# 4_-RF.net
KiCad netlist of a schematic drawn in Altium Designer
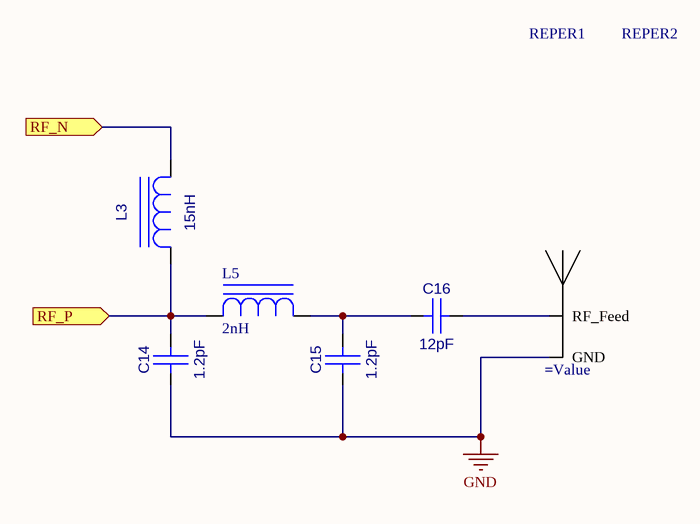
[diagram p0: [4]-RF.SchDoc]

(export (version "E")
  (design (tool "Eeschema 10.0.6"))
  (components
    (comp (ref "=Value")
      (value "ANTENNA_IFA_245_1MM")
      (footprint "IFA245_1mm")
      (description "Antenna 2.45GHz")
      (libsource (lib "fizik_lib") (part "ANTENNA_IFA_245_1MM"))
    )
    (comp (ref "C14")
      (value "1.2pF")
      (footprint "CC0603")
      (description "CC0603")
      (libsource (lib "gprs_modem_2") (part "CC0603"))
    )
    (comp (ref "C15")
      (value "1.2pF")
      (footprint "CC0603")
      (description "CC0603")
      (libsource (lib "gprs_modem_2") (part "CC0603"))
    )
    (comp (ref "C16")
      (value "12pF")
      (footprint "CC0603")
      (description "CC0603")
      (libsource (lib "gprs_modem_2") (part "CC0603"))
    )
    (comp (ref "L3")
      (value "15nH")
      (footprint "L0603")
      (description "L0603")
      (libsource (lib "fizik_lib") (part "L0603"))
    )
    (comp (ref "L5")
      (value "2nH")
      (footprint "L0402")
      (description "L0402")
      (libsource (lib "gprs_modem_2") (part "L0402"))
    )
    (comp (ref "REPER1")
      (value "REPER1.2")
      (footprint "REPER1.2")
      (libsource (lib "gprs_modem_2") (part "REPER1.2"))
    )
    (comp (ref "REPER2")
      (value "REPER1.2")
      (footprint "REPER1.2")
      (libsource (lib "gprs_modem_2") (part "REPER1.2"))
    )
  )
  (nets
    (net (code "1") (name "/RF_N") (class "Default")
      (node (ref "L3") (pin "2") (pinfunction "C_2") (pintype "passive"))
    )
    (net (code "2") (name "/RF_P") (class "Default")
      (node (ref "C14") (pin "2") (pinfunction "B_2") (pintype "passive"))
      (node (ref "L3") (pin "1") (pinfunction "A_1") (pintype "passive"))
      (node (ref "L5") (pin "1") (pinfunction "A_1") (pintype "passive"))
    )
    (net (code "3") (name "GND") (class "Default")
      (node (ref "=Value") (pin "2") (pinfunction "GND_2") (pintype "passive"))
      (node (ref "C14") (pin "1") (pinfunction "A_1") (pintype "passive"))
      (node (ref "C15") (pin "1") (pinfunction "A_1") (pintype "passive"))
    )
    (net (code "4") (name "Net-(=Value-RF_Feed)") (class "Default")
      (node (ref "=Value") (pin "1") (pinfunction "RF_Feed_1") (pintype "passive"))
      (node (ref "C16") (pin "2") (pinfunction "B_2") (pintype "passive"))
    )
    (net (code "5") (name "Net-(C15-B)") (class "Default")
      (node (ref "C15") (pin "2") (pinfunction "B_2") (pintype "passive"))
      (node (ref "C16") (pin "1") (pinfunction "A_1") (pintype "passive"))
      (node (ref "L5") (pin "2") (pinfunction "C_2") (pintype "passive"))
    )
    (net (code "6") (name "unconnected-(REPER1-Pad1)") (class "Default")
      (node (ref "REPER1") (pin "1") (pintype "passive"))
    )
    (net (code "7") (name "unconnected-(REPER2-Pad1)") (class "Default")
      (node (ref "REPER2") (pin "1") (pintype "passive"))
    )
  )
)
